# Switch_Decoderv04a.net
KiCad netlist of a schematic drawn in EAGLE
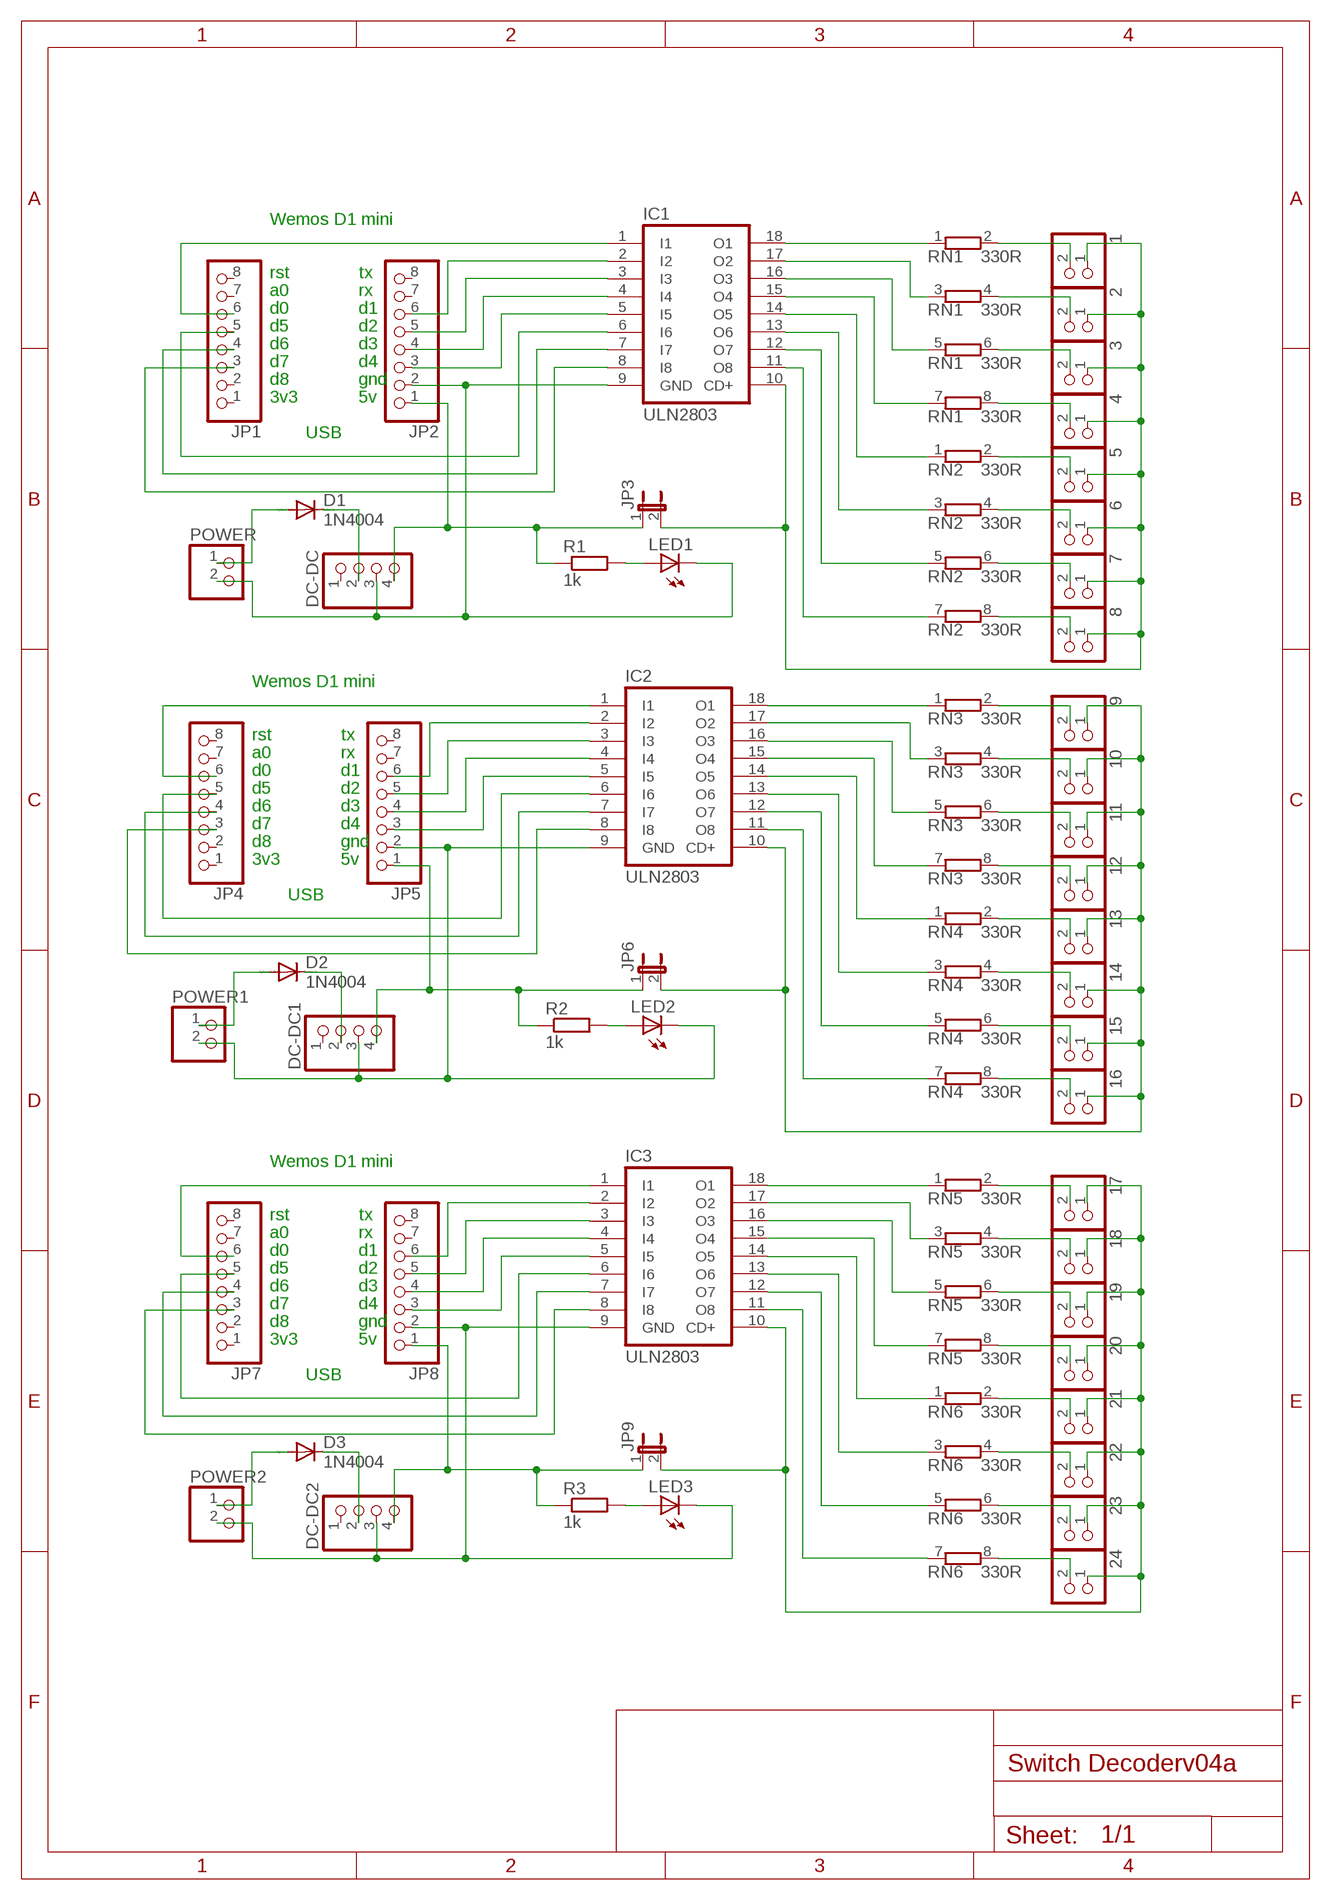
[diagram p0: schematic, sheet 1]

(export (version "E")
  (design (tool "Eeschema 10.0.6"))
  (components
    (comp (ref "1")
      (value "PINHD-1X2")
      (footprint "eagle-import:1X02")
      (libsource (lib "eagle-import") (part "PINHD-1X2"))
    )
    (comp (ref "2")
      (value "PINHD-1X2")
      (footprint "eagle-import:1X02")
      (libsource (lib "eagle-import") (part "PINHD-1X2"))
    )
    (comp (ref "3")
      (value "PINHD-1X2")
      (footprint "eagle-import:1X02")
      (libsource (lib "eagle-import") (part "PINHD-1X2"))
    )
    (comp (ref "4")
      (value "PINHD-1X2")
      (footprint "eagle-import:1X02")
      (libsource (lib "eagle-import") (part "PINHD-1X2"))
    )
    (comp (ref "5")
      (value "PINHD-1X2")
      (footprint "eagle-import:1X02")
      (libsource (lib "eagle-import") (part "PINHD-1X2"))
    )
    (comp (ref "6")
      (value "PINHD-1X2")
      (footprint "eagle-import:1X02")
      (libsource (lib "eagle-import") (part "PINHD-1X2"))
    )
    (comp (ref "7")
      (value "PINHD-1X2")
      (footprint "eagle-import:1X02")
      (libsource (lib "eagle-import") (part "PINHD-1X2"))
    )
    (comp (ref "8")
      (value "PINHD-1X2")
      (footprint "eagle-import:1X02")
      (libsource (lib "eagle-import") (part "PINHD-1X2"))
    )
    (comp (ref "9")
      (value "PINHD-1X2")
      (footprint "eagle-import:1X02")
      (libsource (lib "eagle-import") (part "PINHD-1X2"))
    )
    (comp (ref "10")
      (value "PINHD-1X2")
      (footprint "eagle-import:1X02")
      (libsource (lib "eagle-import") (part "PINHD-1X2"))
    )
    (comp (ref "11")
      (value "PINHD-1X2")
      (footprint "eagle-import:1X02")
      (libsource (lib "eagle-import") (part "PINHD-1X2"))
    )
    (comp (ref "12")
      (value "PINHD-1X2")
      (footprint "eagle-import:1X02")
      (libsource (lib "eagle-import") (part "PINHD-1X2"))
    )
    (comp (ref "13")
      (value "PINHD-1X2")
      (footprint "eagle-import:1X02")
      (libsource (lib "eagle-import") (part "PINHD-1X2"))
    )
    (comp (ref "14")
      (value "PINHD-1X2")
      (footprint "eagle-import:1X02")
      (libsource (lib "eagle-import") (part "PINHD-1X2"))
    )
    (comp (ref "15")
      (value "PINHD-1X2")
      (footprint "eagle-import:1X02")
      (libsource (lib "eagle-import") (part "PINHD-1X2"))
    )
    (comp (ref "16")
      (value "PINHD-1X2")
      (footprint "eagle-import:1X02")
      (libsource (lib "eagle-import") (part "PINHD-1X2"))
    )
    (comp (ref "17")
      (value "PINHD-1X2")
      (footprint "eagle-import:1X02")
      (libsource (lib "eagle-import") (part "PINHD-1X2"))
    )
    (comp (ref "18")
      (value "PINHD-1X2")
      (footprint "eagle-import:1X02")
      (libsource (lib "eagle-import") (part "PINHD-1X2"))
    )
    (comp (ref "19")
      (value "PINHD-1X2")
      (footprint "eagle-import:1X02")
      (libsource (lib "eagle-import") (part "PINHD-1X2"))
    )
    (comp (ref "20")
      (value "PINHD-1X2")
      (footprint "eagle-import:1X02")
      (libsource (lib "eagle-import") (part "PINHD-1X2"))
    )
    (comp (ref "21")
      (value "PINHD-1X2")
      (footprint "eagle-import:1X02")
      (libsource (lib "eagle-import") (part "PINHD-1X2"))
    )
    (comp (ref "22")
      (value "PINHD-1X2")
      (footprint "eagle-import:1X02")
      (libsource (lib "eagle-import") (part "PINHD-1X2"))
    )
    (comp (ref "23")
      (value "PINHD-1X2")
      (footprint "eagle-import:1X02")
      (libsource (lib "eagle-import") (part "PINHD-1X2"))
    )
    (comp (ref "24")
      (value "PINHD-1X2")
      (footprint "eagle-import:1X02")
      (libsource (lib "eagle-import") (part "PINHD-1X2"))
    )
    (comp (ref "D1")
      (value "1N4004")
      (footprint "eagle-import:DO41-10")
      (libsource (lib "eagle-import") (part "1N4004"))
    )
    (comp (ref "D2")
      (value "1N4004")
      (footprint "eagle-import:DO41-10")
      (libsource (lib "eagle-import") (part "1N4004"))
    )
    (comp (ref "D3")
      (value "1N4004")
      (footprint "eagle-import:DO41-10")
      (libsource (lib "eagle-import") (part "1N4004"))
    )
    (comp (ref "DC-DC")
      (value "PINHD-1X4")
      (footprint "eagle-import:1X04")
      (libsource (lib "eagle-import") (part "PINHD-1X4"))
    )
    (comp (ref "DC-DC1")
      (value "PINHD-1X4")
      (footprint "eagle-import:1X04")
      (libsource (lib "eagle-import") (part "PINHD-1X4"))
    )
    (comp (ref "DC-DC2")
      (value "PINHD-1X4")
      (footprint "eagle-import:1X04")
      (libsource (lib "eagle-import") (part "PINHD-1X4"))
    )
    (comp (ref "IC1")
      (value "ULN2803")
      (footprint "eagle-import:DIL18")
      (libsource (lib "eagle-import") (part "ULN2803A"))
    )
    (comp (ref "IC2")
      (value "ULN2803")
      (footprint "eagle-import:DIL18")
      (libsource (lib "eagle-import") (part "ULN2803A"))
    )
    (comp (ref "IC3")
      (value "ULN2803")
      (footprint "eagle-import:DIL18")
      (libsource (lib "eagle-import") (part "ULN2803A"))
    )
    (comp (ref "JP1")
      (value "PINHD-1X8")
      (footprint "eagle-import:1X08")
      (libsource (lib "eagle-import") (part "PINHD-1X8"))
    )
    (comp (ref "JP2")
      (value "PINHD-1X8")
      (footprint "eagle-import:1X08")
      (libsource (lib "eagle-import") (part "PINHD-1X8"))
    )
    (comp (ref "JP3")
      (value "JP1E")
      (footprint "eagle-import:JP1")
      (libsource (lib "eagle-import") (part "JP1E"))
    )
    (comp (ref "JP4")
      (value "PINHD-1X8")
      (footprint "eagle-import:1X08")
      (libsource (lib "eagle-import") (part "PINHD-1X8"))
    )
    (comp (ref "JP5")
      (value "PINHD-1X8")
      (footprint "eagle-import:1X08")
      (libsource (lib "eagle-import") (part "PINHD-1X8"))
    )
    (comp (ref "JP6")
      (value "JP1E")
      (footprint "eagle-import:JP1")
      (libsource (lib "eagle-import") (part "JP1E"))
    )
    (comp (ref "JP7")
      (value "PINHD-1X8")
      (footprint "eagle-import:1X08")
      (libsource (lib "eagle-import") (part "PINHD-1X8"))
    )
    (comp (ref "JP8")
      (value "PINHD-1X8")
      (footprint "eagle-import:1X08")
      (libsource (lib "eagle-import") (part "PINHD-1X8"))
    )
    (comp (ref "JP9")
      (value "JP1E")
      (footprint "eagle-import:JP1")
      (libsource (lib "eagle-import") (part "JP1E"))
    )
    (comp (ref "LED1")
      (value "LED3MM")
      (footprint "eagle-import:LED3MM")
      (libsource (lib "eagle-import") (part "LED3MM"))
    )
    (comp (ref "LED2")
      (value "LED3MM")
      (footprint "eagle-import:LED3MM")
      (libsource (lib "eagle-import") (part "LED3MM"))
    )
    (comp (ref "LED3")
      (value "LED3MM")
      (footprint "eagle-import:LED3MM")
      (libsource (lib "eagle-import") (part "LED3MM"))
    )
    (comp (ref "POWER")
      (value "PINHD-1X2")
      (footprint "eagle-import:1X02")
      (libsource (lib "eagle-import") (part "PINHD-1X2"))
    )
    (comp (ref "POWER1")
      (value "PINHD-1X2")
      (footprint "eagle-import:1X02")
      (libsource (lib "eagle-import") (part "PINHD-1X2"))
    )
    (comp (ref "POWER2")
      (value "PINHD-1X2")
      (footprint "eagle-import:1X02")
      (libsource (lib "eagle-import") (part "PINHD-1X2"))
    )
    (comp (ref "R1")
      (value "1k")
      (footprint "eagle-import:0309_10")
      (libsource (lib "eagle-import") (part "R-EU_0309/10"))
    )
    (comp (ref "R2")
      (value "1k")
      (footprint "eagle-import:0309_10")
      (libsource (lib "eagle-import") (part "R-EU_0309/10"))
    )
    (comp (ref "R3")
      (value "1k")
      (footprint "eagle-import:0309_10")
      (libsource (lib "eagle-import") (part "R-EU_0309/10"))
    )
    (comp (ref "RN1")
      (value "330R")
      (footprint "eagle-import:SIL8")
      (libsource (lib "eagle-import") (part "E4RP"))
    )
    (comp (ref "RN2")
      (value "330R")
      (footprint "eagle-import:SIL8")
      (libsource (lib "eagle-import") (part "E4RP"))
    )
    (comp (ref "RN3")
      (value "330R")
      (footprint "eagle-import:SIL8")
      (libsource (lib "eagle-import") (part "E4RP"))
    )
    (comp (ref "RN4")
      (value "330R")
      (footprint "eagle-import:SIL8")
      (libsource (lib "eagle-import") (part "E4RP"))
    )
    (comp (ref "RN5")
      (value "330R")
      (footprint "eagle-import:SIL8")
      (libsource (lib "eagle-import") (part "E4RP"))
    )
    (comp (ref "RN6")
      (value "330R")
      (footprint "eagle-import:SIL8")
      (libsource (lib "eagle-import") (part "E4RP"))
    )
  )
  (nets
    (net (code "1") (name "Net-(1-Pad2)") (class "Default")
      (node (ref "1") (pin "2") (pinfunction "2_2") (pintype "passive"))
      (node (ref "RN1") (pin "2") (pinfunction "2_2") (pintype "passive"))
    )
    (net (code "2") (name "Net-(5-Pad2)") (class "Default")
      (node (ref "5") (pin "2") (pinfunction "2_2") (pintype "passive"))
      (node (ref "RN2") (pin "2") (pinfunction "2_2") (pintype "passive"))
    )
    (net (code "3") (name "Net-(9-Pad2)") (class "Default")
      (node (ref "9") (pin "2") (pinfunction "2_2") (pintype "passive"))
      (node (ref "RN3") (pin "2") (pinfunction "2_2") (pintype "passive"))
    )
    (net (code "4") (name "Net-(13-Pad2)") (class "Default")
      (node (ref "13") (pin "2") (pinfunction "2_2") (pintype "passive"))
      (node (ref "RN4") (pin "2") (pinfunction "2_2") (pintype "passive"))
    )
    (net (code "5") (name "Net-(17-Pad2)") (class "Default")
      (node (ref "17") (pin "2") (pinfunction "2_2") (pintype "passive"))
      (node (ref "RN5") (pin "2") (pinfunction "2_2") (pintype "passive"))
    )
    (net (code "6") (name "Net-(21-Pad2)") (class "Default")
      (node (ref "21") (pin "2") (pinfunction "2_2") (pintype "passive"))
      (node (ref "RN6") (pin "2") (pinfunction "2_2") (pintype "passive"))
    )
    (net (code "7") (name "Net-(D1-PadA)") (class "Default")
      (node (ref "D1") (pin "A") (pinfunction "A_A") (pintype "passive"))
      (node (ref "POWER") (pin "1") (pinfunction "1_1") (pintype "passive"))
    )
    (net (code "8") (name "Net-(D1-PadC)") (class "Default")
      (node (ref "D1") (pin "C") (pinfunction "C_C") (pintype "passive"))
      (node (ref "DC-DC") (pin "2") (pinfunction "2_2") (pintype "passive"))
    )
    (net (code "9") (name "Net-(D2-PadA)") (class "Default")
      (node (ref "D2") (pin "A") (pinfunction "A_A") (pintype "passive"))
      (node (ref "POWER1") (pin "1") (pinfunction "1_1") (pintype "passive"))
    )
    (net (code "10") (name "Net-(D2-PadC)") (class "Default")
      (node (ref "D2") (pin "C") (pinfunction "C_C") (pintype "passive"))
      (node (ref "DC-DC1") (pin "2") (pinfunction "2_2") (pintype "passive"))
    )
    (net (code "11") (name "Net-(D3-PadA)") (class "Default")
      (node (ref "D3") (pin "A") (pinfunction "A_A") (pintype "passive"))
      (node (ref "POWER2") (pin "1") (pinfunction "1_1") (pintype "passive"))
    )
    (net (code "12") (name "Net-(D3-PadC)") (class "Default")
      (node (ref "D3") (pin "C") (pinfunction "C_C") (pintype "passive"))
      (node (ref "DC-DC2") (pin "2") (pinfunction "2_2") (pintype "passive"))
    )
    (net (code "13") (name "Net-(DC-DC-Pad4)") (class "Default")
      (node (ref "DC-DC") (pin "4") (pinfunction "4_4") (pintype "passive"))
      (node (ref "JP2") (pin "1") (pinfunction "1_1") (pintype "passive"))
      (node (ref "JP3") (pin "1") (pinfunction "1_1") (pintype "passive"))
      (node (ref "R1") (pin "1") (pinfunction "1_1") (pintype "passive"))
    )
    (net (code "14") (name "Net-(DC-DC1-Pad4)") (class "Default")
      (node (ref "DC-DC1") (pin "4") (pinfunction "4_4") (pintype "passive"))
      (node (ref "JP5") (pin "1") (pinfunction "1_1") (pintype "passive"))
      (node (ref "JP6") (pin "1") (pinfunction "1_1") (pintype "passive"))
      (node (ref "R2") (pin "1") (pinfunction "1_1") (pintype "passive"))
    )
    (net (code "15") (name "Net-(DC-DC2-Pad4)") (class "Default")
      (node (ref "DC-DC2") (pin "4") (pinfunction "4_4") (pintype "passive"))
      (node (ref "JP8") (pin "1") (pinfunction "1_1") (pintype "passive"))
      (node (ref "JP9") (pin "1") (pinfunction "1_1") (pintype "passive"))
      (node (ref "R3") (pin "1") (pinfunction "1_1") (pintype "passive"))
    )
    (net (code "16") (name "Net-(IC1-CD+)") (class "Default")
      (node (ref "1") (pin "1") (pinfunction "1_1") (pintype "passive"))
      (node (ref "2") (pin "1") (pinfunction "1_1") (pintype "passive"))
      (node (ref "3") (pin "1") (pinfunction "1_1") (pintype "passive"))
      (node (ref "4") (pin "1") (pinfunction "1_1") (pintype "passive"))
      (node (ref "5") (pin "1") (pinfunction "1_1") (pintype "passive"))
      (node (ref "6") (pin "1") (pinfunction "1_1") (pintype "passive"))
      (node (ref "7") (pin "1") (pinfunction "1_1") (pintype "passive"))
      (node (ref "8") (pin "1") (pinfunction "1_1") (pintype "passive"))
      (node (ref "IC1") (pin "10") (pinfunction "CD+_10") (pintype "passive"))
      (node (ref "JP3") (pin "2") (pinfunction "2_2") (pintype "passive"))
    )
    (net (code "17") (name "Net-(IC1-GND)") (class "Default")
      (node (ref "DC-DC") (pin "3") (pinfunction "3_3") (pintype "passive"))
      (node (ref "IC1") (pin "9") (pinfunction "GND_9") (pintype "power_in"))
      (node (ref "JP2") (pin "2") (pinfunction "2_2") (pintype "passive"))
      (node (ref "LED1") (pin "K") (pinfunction "C_K") (pintype "passive"))
      (node (ref "POWER") (pin "2") (pinfunction "2_2") (pintype "passive"))
    )
    (net (code "18") (name "Net-(IC1-I1)") (class "Default")
      (node (ref "IC1") (pin "1") (pinfunction "I1_1") (pintype "input"))
      (node (ref "JP1") (pin "6") (pinfunction "6_6") (pintype "passive"))
    )
    (net (code "19") (name "Net-(IC1-I2)") (class "Default")
      (node (ref "IC1") (pin "2") (pinfunction "I2_2") (pintype "input"))
      (node (ref "JP2") (pin "6") (pinfunction "6_6") (pintype "passive"))
    )
    (net (code "20") (name "Net-(IC1-I3)") (class "Default")
      (node (ref "IC1") (pin "3") (pinfunction "I3_3") (pintype "input"))
      (node (ref "JP2") (pin "5") (pinfunction "5_5") (pintype "passive"))
    )
    (net (code "21") (name "Net-(IC1-I4)") (class "Default")
      (node (ref "IC1") (pin "4") (pinfunction "I4_4") (pintype "input"))
      (node (ref "JP2") (pin "4") (pinfunction "4_4") (pintype "passive"))
    )
    (net (code "22") (name "Net-(IC1-I5)") (class "Default")
      (node (ref "IC1") (pin "5") (pinfunction "I5_5") (pintype "input"))
      (node (ref "JP2") (pin "3") (pinfunction "3_3") (pintype "passive"))
    )
    (net (code "23") (name "Net-(IC1-I6)") (class "Default")
      (node (ref "IC1") (pin "6") (pinfunction "I6_6") (pintype "input"))
      (node (ref "JP1") (pin "5") (pinfunction "5_5") (pintype "passive"))
    )
    (net (code "24") (name "Net-(IC1-I7)") (class "Default")
      (node (ref "IC1") (pin "7") (pinfunction "I7_7") (pintype "input"))
      (node (ref "JP1") (pin "4") (pinfunction "4_4") (pintype "passive"))
    )
    (net (code "25") (name "Net-(IC1-I8)") (class "Default")
      (node (ref "IC1") (pin "8") (pinfunction "I8_8") (pintype "input"))
      (node (ref "JP1") (pin "3") (pinfunction "3_3") (pintype "passive"))
    )
    (net (code "26") (name "Net-(IC1-O1)") (class "Default")
      (node (ref "IC1") (pin "18") (pinfunction "O1_18") (pintype "open_collector"))
      (node (ref "RN1") (pin "1") (pinfunction "1_1") (pintype "passive"))
    )
    (net (code "27") (name "Net-(IC1-O2)") (class "Default")
      (node (ref "IC1") (pin "17") (pinfunction "O2_17") (pintype "open_collector"))
      (node (ref "RN1") (pin "3") (pinfunction "1_3") (pintype "passive"))
    )
    (net (code "28") (name "Net-(IC1-O3)") (class "Default")
      (node (ref "IC1") (pin "16") (pinfunction "O3_16") (pintype "open_collector"))
      (node (ref "RN1") (pin "5") (pinfunction "1_5") (pintype "passive"))
    )
    (net (code "29") (name "Net-(IC1-O4)") (class "Default")
      (node (ref "IC1") (pin "15") (pinfunction "O4_15") (pintype "open_collector"))
      (node (ref "RN1") (pin "7") (pinfunction "1_7") (pintype "passive"))
    )
    (net (code "30") (name "Net-(IC1-O5)") (class "Default")
      (node (ref "IC1") (pin "14") (pinfunction "O5_14") (pintype "open_collector"))
      (node (ref "RN2") (pin "1") (pinfunction "1_1") (pintype "passive"))
    )
    (net (code "31") (name "Net-(IC1-O6)") (class "Default")
      (node (ref "IC1") (pin "13") (pinfunction "O6_13") (pintype "open_collector"))
      (node (ref "RN2") (pin "3") (pinfunction "1_3") (pintype "passive"))
    )
    (net (code "32") (name "Net-(IC1-O7)") (class "Default")
      (node (ref "IC1") (pin "12") (pinfunction "O7_12") (pintype "open_collector"))
      (node (ref "RN2") (pin "5") (pinfunction "1_5") (pintype "passive"))
    )
    (net (code "33") (name "Net-(IC1-O8)") (class "Default")
      (node (ref "IC1") (pin "11") (pinfunction "O8_11") (pintype "open_collector"))
      (node (ref "RN2") (pin "7") (pinfunction "1_7") (pintype "passive"))
    )
    (net (code "34") (name "Net-(IC2-CD+)") (class "Default")
      (node (ref "10") (pin "1") (pinfunction "1_1") (pintype "passive"))
      (node (ref "11") (pin "1") (pinfunction "1_1") (pintype "passive"))
      (node (ref "12") (pin "1") (pinfunction "1_1") (pintype "passive"))
      (node (ref "13") (pin "1") (pinfunction "1_1") (pintype "passive"))
      (node (ref "14") (pin "1") (pinfunction "1_1") (pintype "passive"))
      (node (ref "15") (pin "1") (pinfunction "1_1") (pintype "passive"))
      (node (ref "16") (pin "1") (pinfunction "1_1") (pintype "passive"))
      (node (ref "9") (pin "1") (pinfunction "1_1") (pintype "passive"))
      (node (ref "IC2") (pin "10") (pinfunction "CD+_10") (pintype "passive"))
      (node (ref "JP6") (pin "2") (pinfunction "2_2") (pintype "passive"))
    )
    (net (code "35") (name "Net-(IC2-GND)") (class "Default")
      (node (ref "DC-DC1") (pin "3") (pinfunction "3_3") (pintype "passive"))
      (node (ref "IC2") (pin "9") (pinfunction "GND_9") (pintype "power_in"))
      (node (ref "JP5") (pin "2") (pinfunction "2_2") (pintype "passive"))
      (node (ref "LED2") (pin "K") (pinfunction "C_K") (pintype "passive"))
      (node (ref "POWER1") (pin "2") (pinfunction "2_2") (pintype "passive"))
    )
    (net (code "36") (name "Net-(IC2-I1)") (class "Default")
      (node (ref "IC2") (pin "1") (pinfunction "I1_1") (pintype "input"))
      (node (ref "JP4") (pin "6") (pinfunction "6_6") (pintype "passive"))
    )
    (net (code "37") (name "Net-(IC2-I2)") (class "Default")
      (node (ref "IC2") (pin "2") (pinfunction "I2_2") (pintype "input"))
      (node (ref "JP5") (pin "6") (pinfunction "6_6") (pintype "passive"))
    )
    (net (code "38") (name "Net-(IC2-I3)") (class "Default")
      (node (ref "IC2") (pin "3") (pinfunction "I3_3") (pintype "input"))
      (node (ref "JP5") (pin "5") (pinfunction "5_5") (pintype "passive"))
    )
    (net (code "39") (name "Net-(IC2-I4)") (class "Default")
      (node (ref "IC2") (pin "4") (pinfunction "I4_4") (pintype "input"))
      (node (ref "JP5") (pin "4") (pinfunction "4_4") (pintype "passive"))
    )
    (net (code "40") (name "Net-(IC2-I5)") (class "Default")
      (node (ref "IC2") (pin "5") (pinfunction "I5_5") (pintype "input"))
      (node (ref "JP5") (pin "3") (pinfunction "3_3") (pintype "passive"))
    )
    (net (code "41") (name "Net-(IC2-I6)") (class "Default")
      (node (ref "IC2") (pin "6") (pinfunction "I6_6") (pintype "input"))
      (node (ref "JP4") (pin "5") (pinfunction "5_5") (pintype "passive"))
    )
    (net (code "42") (name "Net-(IC2-I7)") (class "Default")
      (node (ref "IC2") (pin "7") (pinfunction "I7_7") (pintype "input"))
      (node (ref "JP4") (pin "4") (pinfunction "4_4") (pintype "passive"))
    )
    (net (code "43") (name "Net-(IC2-I8)") (class "Default")
      (node (ref "IC2") (pin "8") (pinfunction "I8_8") (pintype "input"))
      (node (ref "JP4") (pin "3") (pinfunction "3_3") (pintype "passive"))
    )
    (net (code "44") (name "Net-(IC2-O1)") (class "Default")
      (node (ref "IC2") (pin "18") (pinfunction "O1_18") (pintype "open_collector"))
      (node (ref "RN3") (pin "1") (pinfunction "1_1") (pintype "passive"))
    )
    (net (code "45") (name "Net-(IC2-O2)") (class "Default")
      (node (ref "IC2") (pin "17") (pinfunction "O2_17") (pintype "open_collector"))
      (node (ref "RN3") (pin "3") (pinfunction "1_3") (pintype "passive"))
    )
    (net (code "46") (name "Net-(IC2-O3)") (class "Default")
      (node (ref "IC2") (pin "16") (pinfunction "O3_16") (pintype "open_collector"))
      (node (ref "RN3") (pin "5") (pinfunction "1_5") (pintype "passive"))
    )
    (net (code "47") (name "Net-(IC2-O4)") (class "Default")
      (node (ref "IC2") (pin "15") (pinfunction "O4_15") (pintype "open_collector"))
      (node (ref "RN3") (pin "7") (pinfunction "1_7") (pintype "passive"))
    )
    (net (code "48") (name "Net-(IC2-O5)") (class "Default")
      (node (ref "IC2") (pin "14") (pinfunction "O5_14") (pintype "open_collector"))
      (node (ref "RN4") (pin "1") (pinfunction "1_1") (pintype "passive"))
    )
    (net (code "49") (name "Net-(IC2-O6)") (class "Default")
      (node (ref "IC2") (pin "13") (pinfunction "O6_13") (pintype "open_collector"))
      (node (ref "RN4") (pin "3") (pinfunction "1_3") (pintype "passive"))
    )
    (net (code "50") (name "Net-(IC2-O7)") (class "Default")
      (node (ref "IC2") (pin "12") (pinfunction "O7_12") (pintype "open_collector"))
      (node (ref "RN4") (pin "5") (pinfunction "1_5") (pintype "passive"))
    )
    (net (code "51") (name "Net-(IC2-O8)") (class "Default")
      (node (ref "IC2") (pin "11") (pinfunction "O8_11") (pintype "open_collector"))
      (node (ref "RN4") (pin "7") (pinfunction "1_7") (pintype "passive"))
    )
    (net (code "52") (name "Net-(IC3-CD+)") (class "Default")
      (node (ref "17") (pin "1") (pinfunction "1_1") (pintype "passive"))
      (node (ref "18") (pin "1") (pinfunction "1_1") (pintype "passive"))
      (node (ref "19") (pin "1") (pinfunction "1_1") (pintype "passive"))
      (node (ref "20") (pin "1") (pinfunction "1_1") (pintype "passive"))
      (node (ref "21") (pin "1") (pinfunction "1_1") (pintype "passive"))
      (node (ref "22") (pin "1") (pinfunction "1_1") (pintype "passive"))
      (node (ref "23") (pin "1") (pinfunction "1_1") (pintype "passive"))
      (node (ref "24") (pin "1") (pinfunction "1_1") (pintype "passive"))
      (node (ref "IC3") (pin "10") (pinfunction "CD+_10") (pintype "passive"))
      (node (ref "JP9") (pin "2") (pinfunction "2_2") (pintype "passive"))
    )
    (net (code "53") (name "Net-(IC3-GND)") (class "Default")
      (node (ref "DC-DC2") (pin "3") (pinfunction "3_3") (pintype "passive"))
      (node (ref "IC3") (pin "9") (pinfunction "GND_9") (pintype "power_in"))
      (node (ref "JP8") (pin "2") (pinfunction "2_2") (pintype "passive"))
      (node (ref "LED3") (pin "K") (pinfunction "C_K") (pintype "passive"))
      (node (ref "POWER2") (pin "2") (pinfunction "2_2") (pintype "passive"))
    )
    (net (code "54") (name "Net-(IC3-I1)") (class "Default")
      (node (ref "IC3") (pin "1") (pinfunction "I1_1") (pintype "input"))
      (node (ref "JP7") (pin "6") (pinfunction "6_6") (pintype "passive"))
    )
    (net (code "55") (name "Net-(IC3-I2)") (class "Default")
      (node (ref "IC3") (pin "2") (pinfunction "I2_2") (pintype "input"))
      (node (ref "JP8") (pin "6") (pinfunction "6_6") (pintype "passive"))
    )
    (net (code "56") (name "Net-(IC3-I3)") (class "Default")
      (node (ref "IC3") (pin "3") (pinfunction "I3_3") (pintype "input"))
      (node (ref "JP8") (pin "5") (pinfunction "5_5") (pintype "passive"))
    )
    (net (code "57") (name "Net-(IC3-I4)") (class "Default")
      (node (ref "IC3") (pin "4") (pinfunction "I4_4") (pintype "input"))
      (node (ref "JP8") (pin "4") (pinfunction "4_4") (pintype "passive"))
    )
    (net (code "58") (name "Net-(IC3-I5)") (class "Default")
      (node (ref "IC3") (pin "5") (pinfunction "I5_5") (pintype "input"))
      (node (ref "JP8") (pin "3") (pinfunction "3_3") (pintype "passive"))
    )
    (net (code "59") (name "Net-(IC3-I6)") (class "Default")
      (node (ref "IC3") (pin "6") (pinfunction "I6_6") (pintype "input"))
      (node (ref "JP7") (pin "5") (pinfunction "5_5") (pintype "passive"))
    )
    (net (code "60") (name "Net-(IC3-I7)") (class "Default")
      (node (ref "IC3") (pin "7") (pinfunction "I7_7") (pintype "input"))
      (node (ref "JP7") (pin "4") (pinfunction "4_4") (pintype "passive"))
    )
    (net (code "61") (name "Net-(IC3-I8)") (class "Default")
      (node (ref "IC3") (pin "8") (pinfunction "I8_8") (pintype "input"))
      (node (ref "JP7") (pin "3") (pinfunction "3_3") (pintype "passive"))
    )
    (net (code "62") (name "Net-(IC3-O1)") (class "Default")
      (node (ref "IC3") (pin "18") (pinfunction "O1_18") (pintype "open_collector"))
      (node (ref "RN5") (pin "1") (pinfunction "1_1") (pintype "passive"))
    )
    (net (code "63") (name "Net-(IC3-O2)") (class "Default")
      (node (ref "IC3") (pin "17") (pinfunction "O2_17") (pintype "open_collector"))
      (node (ref "RN5") (pin "3") (pinfunction "1_3") (pintype "passive"))
    )
    (net (code "64") (name "Net-(IC3-O3)") (class "Default")
      (node (ref "IC3") (pin "16") (pinfunction "O3_16") (pintype "open_collector"))
      (node (ref "RN5") (pin "5") (pinfunction "1_5") (pintype "passive"))
    )
    (net (code "65") (name "Net-(IC3-O4)") (class "Default")
      (node (ref "IC3") (pin "15") (pinfunction "O4_15") (pintype "open_collector"))
      (node (ref "RN5") (pin "7") (pinfunction "1_7") (pintype "passive"))
    )
    (net (code "66") (name "Net-(IC3-O5)") (class "Default")
      (node (ref "IC3") (pin "14") (pinfunction "O5_14") (pintype "open_collector"))
      (node (ref "RN6") (pin "1") (pinfunction "1_1") (pintype "passive"))
    )
    (net (code "67") (name "Net-(IC3-O6)") (class "Default")
      (node (ref "IC3") (pin "13") (pinfunction "O6_13") (pintype "open_collector"))
      (node (ref "RN6") (pin "3") (pinfunction "1_3") (pintype "passive"))
    )
    (net (code "68") (name "Net-(IC3-O7)") (class "Default")
      (node (ref "IC3") (pin "12") (pinfunction "O7_12") (pintype "open_collector"))
      (node (ref "RN6") (pin "5") (pinfunction "1_5") (pintype "passive"))
    )
    (net (code "69") (name "Net-(IC3-O8)") (class "Default")
      (node (ref "IC3") (pin "11") (pinfunction "O8_11") (pintype "open_collector"))
      (node (ref "RN6") (pin "7") (pinfunction "1_7") (pintype "passive"))
    )
    (net (code "70") (name "Net-(LED1-PadA)") (class "Default")
      (node (ref "LED1") (pin "A") (pinfunction "A_A") (pintype "passive"))
      (node (ref "R1") (pin "2") (pinfunction "2_2") (pintype "passive"))
    )
    (net (code "71") (name "Net-(LED2-PadA)") (class "Default")
      (node (ref "LED2") (pin "A") (pinfunction "A_A") (pintype "passive"))
      (node (ref "R2") (pin "2") (pinfunction "2_2") (pintype "passive"))
    )
    (net (code "72") (name "Net-(LED3-PadA)") (class "Default")
      (node (ref "LED3") (pin "A") (pinfunction "A_A") (pintype "passive"))
      (node (ref "R3") (pin "2") (pinfunction "2_2") (pintype "passive"))
    )
    (net (code "73") (name "Net-(RN1B-2)") (class "Default")
      (node (ref "2") (pin "2") (pinfunction "2_2") (pintype "passive"))
      (node (ref "RN1") (pin "4") (pinfunction "2_4") (pintype "passive"))
    )
    (net (code "74") (name "Net-(RN1C-2)") (class "Default")
      (node (ref "3") (pin "2") (pinfunction "2_2") (pintype "passive"))
      (node (ref "RN1") (pin "6") (pinfunction "2_6") (pintype "passive"))
    )
    (net (code "75") (name "Net-(RN1D-2)") (class "Default")
      (node (ref "4") (pin "2") (pinfunction "2_2") (pintype "passive"))
      (node (ref "RN1") (pin "8") (pinfunction "2_8") (pintype "passive"))
    )
    (net (code "76") (name "Net-(RN2B-2)") (class "Default")
      (node (ref "6") (pin "2") (pinfunction "2_2") (pintype "passive"))
      (node (ref "RN2") (pin "4") (pinfunction "2_4") (pintype "passive"))
    )
    (net (code "77") (name "Net-(RN2C-2)") (class "Default")
      (node (ref "7") (pin "2") (pinfunction "2_2") (pintype "passive"))
      (node (ref "RN2") (pin "6") (pinfunction "2_6") (pintype "passive"))
    )
    (net (code "78") (name "Net-(RN2D-2)") (class "Default")
      (node (ref "8") (pin "2") (pinfunction "2_2") (pintype "passive"))
      (node (ref "RN2") (pin "8") (pinfunction "2_8") (pintype "passive"))
    )
    (net (code "79") (name "Net-(RN3B-2)") (class "Default")
      (node (ref "10") (pin "2") (pinfunction "2_2") (pintype "passive"))
      (node (ref "RN3") (pin "4") (pinfunction "2_4") (pintype "passive"))
    )
    (net (code "80") (name "Net-(RN3C-2)") (class "Default")
      (node (ref "11") (pin "2") (pinfunction "2_2") (pintype "passive"))
      (node (ref "RN3") (pin "6") (pinfunction "2_6") (pintype "passive"))
    )
    (net (code "81") (name "Net-(RN3D-2)") (class "Default")
      (node (ref "12") (pin "2") (pinfunction "2_2") (pintype "passive"))
      (node (ref "RN3") (pin "8") (pinfunction "2_8") (pintype "passive"))
    )
    (net (code "82") (name "Net-(RN4B-2)") (class "Default")
      (node (ref "14") (pin "2") (pinfunction "2_2") (pintype "passive"))
      (node (ref "RN4") (pin "4") (pinfunction "2_4") (pintype "passive"))
    )
    (net (code "83") (name "Net-(RN4C-2)") (class "Default")
      (node (ref "15") (pin "2") (pinfunction "2_2") (pintype "passive"))
      (node (ref "RN4") (pin "6") (pinfunction "2_6") (pintype "passive"))
    )
    (net (code "84") (name "Net-(RN4D-2)") (class "Default")
      (node (ref "16") (pin "2") (pinfunction "2_2") (pintype "passive"))
      (node (ref "RN4") (pin "8") (pinfunction "2_8") (pintype "passive"))
    )
    (net (code "85") (name "Net-(RN5B-2)") (class "Default")
      (node (ref "18") (pin "2") (pinfunction "2_2") (pintype "passive"))
      (node (ref "RN5") (pin "4") (pinfunction "2_4") (pintype "passive"))
    )
    (net (code "86") (name "Net-(RN5C-2)") (class "Default")
      (node (ref "19") (pin "2") (pinfunction "2_2") (pintype "passive"))
      (node (ref "RN5") (pin "6") (pinfunction "2_6") (pintype "passive"))
    )
    (net (code "87") (name "Net-(RN5D-2)") (class "Default")
      (node (ref "20") (pin "2") (pinfunction "2_2") (pintype "passive"))
      (node (ref "RN5") (pin "8") (pinfunction "2_8") (pintype "passive"))
    )
    (net (code "88") (name "Net-(RN6B-2)") (class "Default")
      (node (ref "22") (pin "2") (pinfunction "2_2") (pintype "passive"))
      (node (ref "RN6") (pin "4") (pinfunction "2_4") (pintype "passive"))
    )
    (net (code "89") (name "Net-(RN6C-2)") (class "Default")
      (node (ref "23") (pin "2") (pinfunction "2_2") (pintype "passive"))
      (node (ref "RN6") (pin "6") (pinfunction "2_6") (pintype "passive"))
    )
    (net (code "90") (name "Net-(RN6D-2)") (class "Default")
      (node (ref "24") (pin "2") (pinfunction "2_2") (pintype "passive"))
      (node (ref "RN6") (pin "8") (pinfunction "2_8") (pintype "passive"))
    )
    (net (code "91") (name "unconnected-(DC-DC-Pad1)") (class "Default")
      (node (ref "DC-DC") (pin "1") (pinfunction "1_1") (pintype "passive"))
    )
    (net (code "92") (name "unconnected-(DC-DC1-Pad1)") (class "Default")
      (node (ref "DC-DC1") (pin "1") (pinfunction "1_1") (pintype "passive"))
    )
    (net (code "93") (name "unconnected-(DC-DC2-Pad1)") (class "Default")
      (node (ref "DC-DC2") (pin "1") (pinfunction "1_1") (pintype "passive"))
    )
    (net (code "94") (name "unconnected-(JP1-Pad1)") (class "Default")
      (node (ref "JP1") (pin "1") (pinfunction "1_1") (pintype "passive"))
    )
    (net (code "95") (name "unconnected-(JP1-Pad2)") (class "Default")
      (node (ref "JP1") (pin "2") (pinfunction "2_2") (pintype "passive"))
    )
    (net (code "96") (name "unconnected-(JP1-Pad7)") (class "Default")
      (node (ref "JP1") (pin "7") (pinfunction "7_7") (pintype "passive"))
    )
    (net (code "97") (name "unconnected-(JP1-Pad8)") (class "Default")
      (node (ref "JP1") (pin "8") (pinfunction "8_8") (pintype "passive"))
    )
    (net (code "98") (name "unconnected-(JP2-Pad7)") (class "Default")
      (node (ref "JP2") (pin "7") (pinfunction "7_7") (pintype "passive"))
    )
    (net (code "99") (name "unconnected-(JP2-Pad8)") (class "Default")
      (node (ref "JP2") (pin "8") (pinfunction "8_8") (pintype "passive"))
    )
    (net (code "100") (name "unconnected-(JP4-Pad1)") (class "Default")
      (node (ref "JP4") (pin "1") (pinfunction "1_1") (pintype "passive"))
    )
    (net (code "101") (name "unconnected-(JP4-Pad2)") (class "Default")
      (node (ref "JP4") (pin "2") (pinfunction "2_2") (pintype "passive"))
    )
    (net (code "102") (name "unconnected-(JP4-Pad7)") (class "Default")
      (node (ref "JP4") (pin "7") (pinfunction "7_7") (pintype "passive"))
    )
    (net (code "103") (name "unconnected-(JP4-Pad8)") (class "Default")
      (node (ref "JP4") (pin "8") (pinfunction "8_8") (pintype "passive"))
    )
    (net (code "104") (name "unconnected-(JP5-Pad7)") (class "Default")
      (node (ref "JP5") (pin "7") (pinfunction "7_7") (pintype "passive"))
    )
    (net (code "105") (name "unconnected-(JP5-Pad8)") (class "Default")
      (node (ref "JP5") (pin "8") (pinfunction "8_8") (pintype "passive"))
    )
    (net (code "106") (name "unconnected-(JP7-Pad1)") (class "Default")
      (node (ref "JP7") (pin "1") (pinfunction "1_1") (pintype "passive"))
    )
    (net (code "107") (name "unconnected-(JP7-Pad2)") (class "Default")
      (node (ref "JP7") (pin "2") (pinfunction "2_2") (pintype "passive"))
    )
    (net (code "108") (name "unconnected-(JP7-Pad7)") (class "Default")
      (node (ref "JP7") (pin "7") (pinfunction "7_7") (pintype "passive"))
    )
    (net (code "109") (name "unconnected-(JP7-Pad8)") (class "Default")
      (node (ref "JP7") (pin "8") (pinfunction "8_8") (pintype "passive"))
    )
    (net (code "110") (name "unconnected-(JP8-Pad7)") (class "Default")
      (node (ref "JP8") (pin "7") (pinfunction "7_7") (pintype "passive"))
    )
    (net (code "111") (name "unconnected-(JP8-Pad8)") (class "Default")
      (node (ref "JP8") (pin "8") (pinfunction "8_8") (pintype "passive"))
    )
  )
)
